# Plaque_Layout.net
KiCad netlist of a schematic drawn in Altium Designer
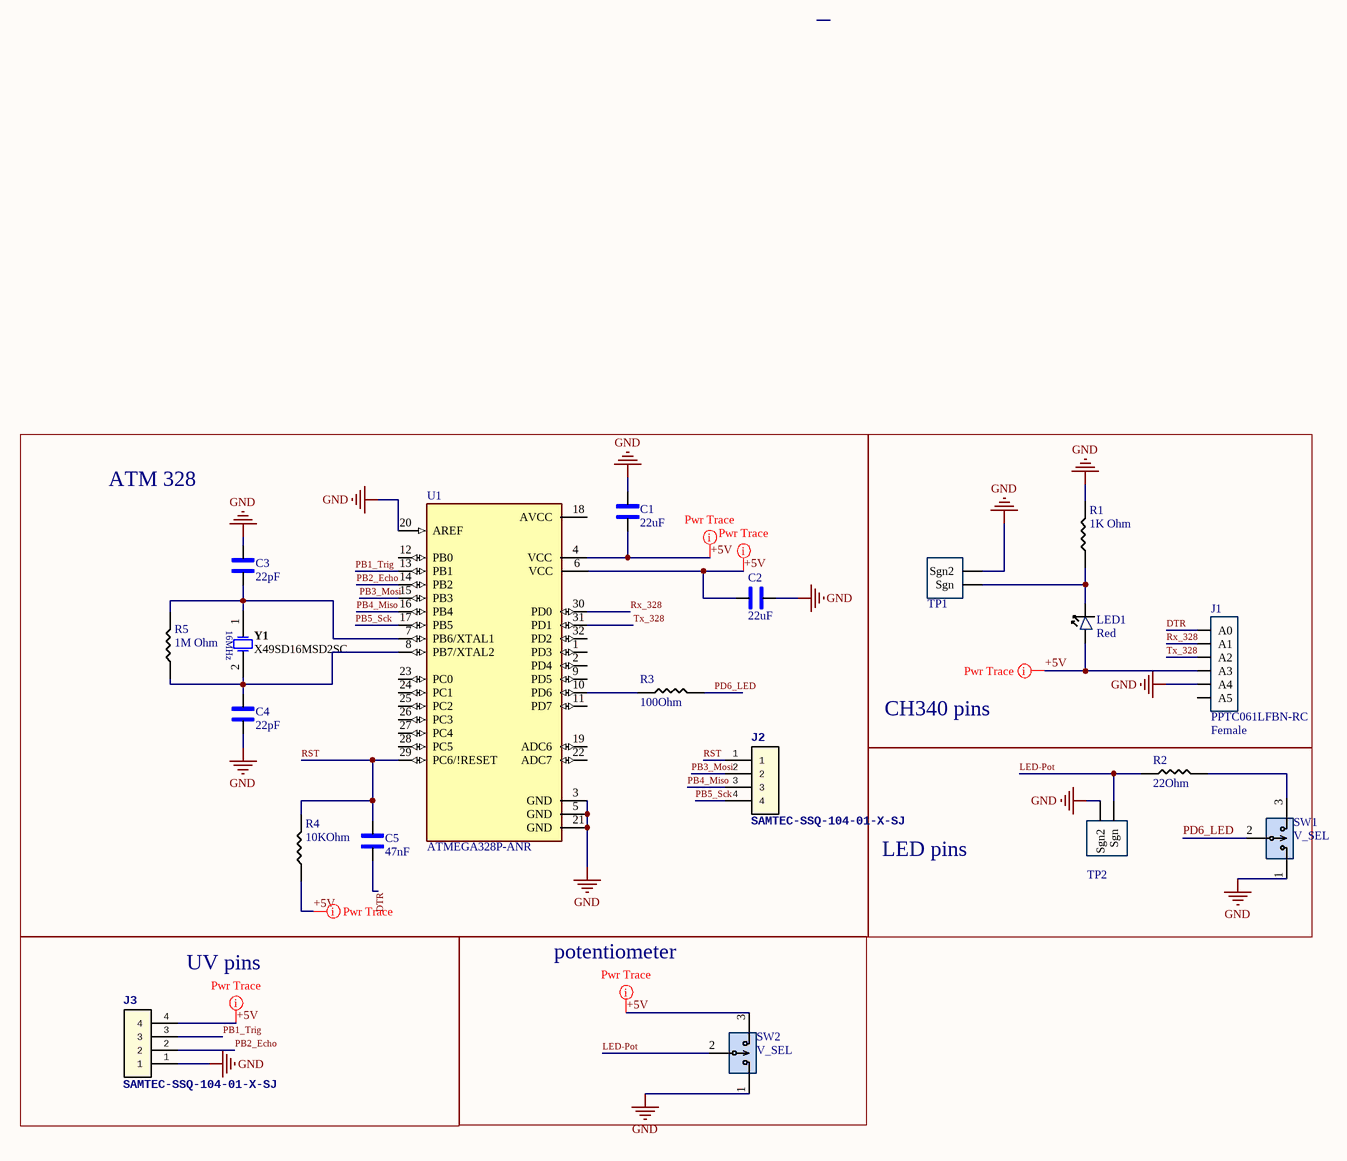
[diagram p0: Plaque_Layout.SchDoc]

(export (version "E")
  (design (tool "Eeschema 10.0.6"))
  (components
    (comp (ref "C1")
      (value "22uF")
      (footprint "1206_Passive_Capacitor")
      (description "22uF ±10% 25V X5R 1206 Multilayer Ceramic Capacitors MLCC - SMD/SMT RoHS")
      (fields (field (name "MFR PART #") "CL31A226KAHNNNE") (field (name "LCSC PART#") "C12891"))
      (libsource (lib "Capstone_Stock_Library") (part "C_22uF_1206"))
    )
    (comp (ref "C2")
      (value "22uF")
      (footprint "1206_Passive_Capacitor")
      (description "22uF ±10% 25V X5R 1206 Multilayer Ceramic Capacitors MLCC - SMD/SMT RoHS")
      (fields (field (name "MFR PART #") "CL31A226KAHNNNE") (field (name "LCSC PART#") "C12891"))
      (libsource (lib "Capstone_Stock_Library") (part "C_22uF_1206"))
    )
    (comp (ref "C3")
      (value "22pF")
      (footprint "1206_Passive_Capacitor")
      (description "50V 22pF C0G ±5% 1206 Multilayer Ceramic Capacitors MLCC - SMD/SMT ROHS")
      (fields (field (name "LCSC PART#") "C107174") (field (name "MFR PART #") "CC1206JKNPOCBN220"))
      (libsource (lib "Capstone_Stock_Library") (part "C_22pF_1206"))
    )
    (comp (ref "C4")
      (value "22pF")
      (footprint "1206_Passive_Capacitor")
      (description "50V 22pF C0G ±5% 1206 Multilayer Ceramic Capacitors MLCC - SMD/SMT ROHS")
      (fields (field (name "LCSC PART#") "C107174") (field (name "MFR PART #") "CC1206JKNPOCBN220"))
      (libsource (lib "Capstone_Stock_Library") (part "C_22pF_1206"))
    )
    (comp (ref "C5")
      (value "47nF")
      (footprint "1206_Passive_Capacitor")
      (description "10nF 50V X7R ±10% 1206 Multilayer Ceramic Capacitors MLCC - SMD/SMT ROHS")
      (fields (field (name "MFR PART #") "CL31B105KBHNNNE") (field (name "LCSC PART#") "C1848"))
      (libsource (lib "Capstone_Stock_Library") (part "C_10nF_1206"))
    )
    (comp (ref "J1")
      (value "PPTC061LFBN-RC")
      (footprint "6_PIN_ARD-Analog_100mil")
      (description "6 Position Header Connector 0.100\" (2.54mm) Through Hole Tin")
      (fields (field (name "LCSC PART#") "C40877") (field (name "ALTIUM_VALUE") "Female"))
      (libsource (lib "Capstone_Stock_Library") (part "JF_6_PIN_FEMA_ARD-Anolog"))
    )
    (comp (ref "J2")
      (value "SAMTEC-SSQ-104-01-X-SJ")
      (footprint "JF-4_SSQ-104-01-X-S")
      (fields (field (name "MFR PART #") "SSQ-104-01-X-SJ") (field (name "LCSC PART#") "C2718488"))
      (libsource (lib "") (part "JF_4_PIN_FEMALE_1"))
    )
    (comp (ref "J3")
      (value "SAMTEC-SSQ-104-01-X-SJ")
      (footprint "JF-4_SSQ-104-01-X-S")
      (fields (field (name "MFR PART #") "SSQ-104-01-X-SJ") (field (name "LCSC PART#") "C2718488"))
      (libsource (lib "Capstone_Stock_Library") (part "JF_4_PIN_FEMALE"))
    )
    (comp (ref "LED1")
      (value "Red")
      (footprint "LED_1206")
      (description "Red 621~631nm 1206 Light Emitting Diodes (LED) RoHS")
      (fields (field (name "MFR PART #") "15-21/R6C-FQ1R1B/2T") (field (name "LCSC PART#") "C93133"))
      (libsource (lib "Capstone_Stock_Library") (part "LED_RED_1206"))
    )
    (comp (ref "R1")
      (value "1K Ohm")
      (footprint "1206_Passive_Resitor")
      (description "CHIP RESISTOR - SURFACE MOUNT 1KOHMS ±1% 1/4W 1206 ROHS")
      (fields (field (name "MFR PART #") "RNCP1206FTD1K00CT") (field (name "LCSC PART#") "C4410"))
      (libsource (lib "Capstone_Stock_Library") (part "R_1K_1206"))
    )
    (comp (ref "R2")
      (value "22Ohm")
      (footprint "1206_Passive_Resitor")
      (description "1Ω ±5% 0.25W ±400ppm/℃ 1206 Chip Resistor - Surface Mount RoHS")
      (fields (field (name "LCSC PART#") "C1409") (field (name "MFR PART #") "1206W4J010JT5E"))
      (libsource (lib "Capstone_Stock_Library") (part "R_1_1206"))
    )
    (comp (ref "R3")
      (value "100Ohm")
      (footprint "1206_Passive_Resitor")
      (description "100Ω ±1% 0.25W ±100ppm/℃ 1206 Chip Resistor - Surface Mount RoHS")
      (fields (field (name "LCSC PART#") "C17901") (field (name "MFR PART #") "1206W4F1000T5E"))
      (libsource (lib "Capstone_Stock_Library") (part "R_100_1206"))
    )
    (comp (ref "R4")
      (value "10KOhm")
      (footprint "1206_Passive_Resitor")
      (description "10 kOhms ±5% 0.25W, 1/4W Chip Resistor 1206 (3216 Metric) Automotive AEC-Q200 Thick Film")
      (fields (field (name "MFR PART #") "RMCF1206FT10K0") (field (name "LCSC PART#") "C17902"))
      (libsource (lib "Capstone_Stock_Library") (part "R_10K_1206"))
    )
    (comp (ref "R5")
      (value "1M Ohm")
      (footprint "1206_Passive_Resitor")
      (description "CHIP RESISTOR - SURFACE MOUNT 1MOHMS ±1% 1/4W 1206 ROHS")
      (fields (field (name "MFR PART #") "RMCF1206JT1M00") (field (name "LCSC PART#") "C17927"))
      (libsource (lib "Capstone_Stock_Library") (part "R_1M_1206"))
    )
    (comp (ref "SW1")
      (value "V_SEL")
      (footprint "3_PIN_100mil")
      (description "Connector Header Through Hole 3 position 0.100\" (2.54mm)")
      (fields (field (name "MFR PART #") "PREC003SAAN-RC") (field (name "LCSC PART#") "C49257"))
      (libsource (lib "328_Arduino_Library") (part "SW_3Pin_100mil_Switch"))
    )
    (comp (ref "SW2")
      (value "V_SEL")
      (footprint "3_PIN_100mil")
      (description "Connector Header Through Hole 3 position 0.100\" (2.54mm)")
      (fields (field (name "MFR PART #") "PREC003SAAN-RC") (field (name "LCSC PART#") "C49257"))
      (libsource (lib "328_Arduino_Library") (part "SW_3Pin_100mil_Switch"))
    )
    (comp (ref "TP1")
      (value "10x Probe TP")
      (footprint "TP_Diff_Probe")
      (description "Test Point 300 mil centers")
      (libsource (lib "") (part "TP_Diff_Probe_1"))
    )
    (comp (ref "TP2")
      (value "10x Probe TP")
      (footprint "TP_Diff_Probe")
      (description "Test Point 300 mil centers")
      (libsource (lib "Capstone_Stock_Library") (part "TP_Diff_Probe"))
    )
    (comp (ref "U1")
      (value "ATMEGA328P-ANR")
      (footprint "ATMega328P")
      (description "AVR AVR® ATmega Microcontroller IC 8-Bit 20MHz 32KB (16K x 16) FLASH 32-TQFP (7x7)")
      (fields (field (name "MFR PART #") "ATMEGA328P-AU") (field (name "LCSC PART#") "C14877"))
      (libsource (lib "Capstone_Stock_Library") (part "U_ATMega328P"))
    )
    (comp (ref "Y1")
      (value "X49SD16MSD2SC")
      (footprint "TH_CRYSTAL")
      (description "16MHz Through Hole Crystal Oscillator (2-pin) 20pF ±20ppm ±30ppm HC-49S Crystals ROHS")
      (fields (field (name "LCSC PART NUMBER") "C16212"))
      (libsource (lib "Capstone_Stock_Library") (part "CRYSTAL_16MHZ_TH_1"))
    )
  )
  (nets
    (net (code "1") (name "/+5V") (class "Default")
      (node (ref "C1") (pin "1") (pinfunction "1_1") (pintype "passive"))
      (node (ref "C2") (pin "1") (pinfunction "1_1") (pintype "passive"))
      (node (ref "J1") (pin "4") (pinfunction "A3_4") (pintype "passive"))
      (node (ref "J3") (pin "4") (pinfunction "4_4") (pintype "passive"))
      (node (ref "LED1") (pin "1") (pinfunction "1_1") (pintype "passive"))
      (node (ref "R4") (pin "1") (pinfunction "1_1") (pintype "passive"))
      (node (ref "SW2") (pin "3") (pinfunction "3_3") (pintype "passive"))
      (node (ref "U1") (pin "4") (pinfunction "VCC_4") (pintype "power_in"))
      (node (ref "U1") (pin "6") (pinfunction "VCC_6") (pintype "power_in"))
    )
    (net (code "2") (name "/DTR") (class "Default")
      (node (ref "C5") (pin "1") (pinfunction "1_1") (pintype "passive"))
      (node (ref "J1") (pin "1") (pinfunction "A0_1") (pintype "passive"))
    )
    (net (code "3") (name "/LED-Pot") (class "Default")
      (node (ref "R2") (pin "1") (pinfunction "1_1") (pintype "passive"))
      (node (ref "SW2") (pin "2") (pinfunction "2_2") (pintype "passive"))
      (node (ref "TP2") (pin "1") (pinfunction "Sgn_1") (pintype "passive"))
    )
    (net (code "4") (name "/PB1_Trig") (class "Default")
      (node (ref "J3") (pin "3") (pinfunction "3_3") (pintype "passive"))
      (node (ref "U1") (pin "13") (pinfunction "PB1_13") (pintype "bidirectional"))
    )
    (net (code "5") (name "/PB2_Echo") (class "Default")
      (node (ref "J3") (pin "2") (pinfunction "2_2") (pintype "passive"))
      (node (ref "U1") (pin "14") (pinfunction "PB2_14") (pintype "bidirectional"))
    )
    (net (code "6") (name "/PB3_Mosi") (class "Default")
      (node (ref "J2") (pin "2") (pinfunction "2_2") (pintype "passive"))
      (node (ref "U1") (pin "15") (pinfunction "PB3_15") (pintype "bidirectional"))
    )
    (net (code "7") (name "/PB4_Miso") (class "Default")
      (node (ref "J2") (pin "3") (pinfunction "3_3") (pintype "passive"))
      (node (ref "U1") (pin "16") (pinfunction "PB4_16") (pintype "bidirectional"))
    )
    (net (code "8") (name "/PB5_Sck") (class "Default")
      (node (ref "J2") (pin "4") (pinfunction "4_4") (pintype "passive"))
      (node (ref "U1") (pin "17") (pinfunction "PB5_17") (pintype "bidirectional"))
    )
    (net (code "9") (name "/PD6_LED") (class "Default")
      (node (ref "R3") (pin "2") (pinfunction "2_2") (pintype "passive"))
      (node (ref "SW1") (pin "2") (pinfunction "2_2") (pintype "passive"))
    )
    (net (code "10") (name "/RST") (class "Default")
      (node (ref "C5") (pin "2") (pinfunction "2_2") (pintype "passive"))
      (node (ref "J2") (pin "1") (pinfunction "1_1") (pintype "passive"))
      (node (ref "R4") (pin "2") (pinfunction "2_2") (pintype "passive"))
      (node (ref "U1") (pin "29") (pinfunction "PC6/!RESET_29") (pintype "bidirectional"))
    )
    (net (code "11") (name "/Rx_328") (class "Default")
      (node (ref "J1") (pin "2") (pinfunction "A1_2") (pintype "passive"))
      (node (ref "U1") (pin "30") (pinfunction "PD0_30") (pintype "bidirectional"))
    )
    (net (code "12") (name "/Tx_328") (class "Default")
      (node (ref "J1") (pin "3") (pinfunction "A2_3") (pintype "passive"))
      (node (ref "U1") (pin "31") (pinfunction "PD1_31") (pintype "bidirectional"))
    )
    (net (code "13") (name "GND") (class "Default")
      (node (ref "C1") (pin "2") (pinfunction "2_2") (pintype "passive"))
      (node (ref "C2") (pin "2") (pinfunction "2_2") (pintype "passive"))
      (node (ref "C3") (pin "2") (pinfunction "2_2") (pintype "passive"))
      (node (ref "C4") (pin "1") (pinfunction "1_1") (pintype "passive"))
      (node (ref "J1") (pin "5") (pinfunction "A4_5") (pintype "passive"))
      (node (ref "J3") (pin "1") (pinfunction "1_1") (pintype "passive"))
      (node (ref "R1") (pin "2") (pinfunction "2_2") (pintype "passive"))
      (node (ref "SW1") (pin "1") (pinfunction "1_1") (pintype "passive"))
      (node (ref "SW2") (pin "1") (pinfunction "1_1") (pintype "passive"))
      (node (ref "TP1") (pin "2") (pinfunction "Sgn2_2") (pintype "passive"))
      (node (ref "TP2") (pin "2") (pinfunction "Sgn2_2") (pintype "passive"))
      (node (ref "U1") (pin "20") (pinfunction "AREF_20") (pintype "input"))
      (node (ref "U1") (pin "21") (pinfunction "GND_21") (pintype "power_in"))
      (node (ref "U1") (pin "3") (pinfunction "GND_3") (pintype "power_in"))
      (node (ref "U1") (pin "5") (pinfunction "GND_5") (pintype "power_in"))
    )
    (net (code "14") (name "Net-(R2-Pad2)") (class "Default")
      (node (ref "R2") (pin "2") (pinfunction "2_2") (pintype "passive"))
      (node (ref "SW1") (pin "3") (pinfunction "3_3") (pintype "passive"))
    )
    (net (code "15") (name "Net-(TP1-Sgn)") (class "Default")
      (node (ref "LED1") (pin "2") (pinfunction "2_2") (pintype "passive"))
      (node (ref "R1") (pin "1") (pinfunction "1_1") (pintype "passive"))
      (node (ref "TP1") (pin "1") (pinfunction "Sgn_1") (pintype "passive"))
    )
    (net (code "16") (name "Net-(U1-PB6{slash}XTAL1)") (class "Default")
      (node (ref "C3") (pin "1") (pinfunction "1_1") (pintype "passive"))
      (node (ref "R5") (pin "2") (pinfunction "2_2") (pintype "passive"))
      (node (ref "U1") (pin "7") (pinfunction "PB6/XTAL1_7") (pintype "bidirectional"))
      (node (ref "Y1") (pin "1") (pinfunction "1_1") (pintype "passive"))
    )
    (net (code "17") (name "Net-(U1-PB7{slash}XTAL2)") (class "Default")
      (node (ref "C4") (pin "2") (pinfunction "2_2") (pintype "passive"))
      (node (ref "R5") (pin "1") (pinfunction "1_1") (pintype "passive"))
      (node (ref "U1") (pin "8") (pinfunction "PB7/XTAL2_8") (pintype "bidirectional"))
      (node (ref "Y1") (pin "2") (pinfunction "2_2") (pintype "passive"))
    )
    (net (code "18") (name "Net-(U1-PD6)") (class "Default")
      (node (ref "R3") (pin "1") (pinfunction "1_1") (pintype "passive"))
      (node (ref "U1") (pin "10") (pinfunction "PD6_10") (pintype "bidirectional"))
    )
    (net (code "19") (name "unconnected-(J1-A5-Pad6)") (class "Default")
      (node (ref "J1") (pin "6") (pinfunction "A5_6") (pintype "passive"))
    )
    (net (code "20") (name "unconnected-(U1-ADC6-Pad19)") (class "Default")
      (node (ref "U1") (pin "19") (pinfunction "ADC6_19") (pintype "bidirectional"))
    )
    (net (code "21") (name "unconnected-(U1-ADC7-Pad22)") (class "Default")
      (node (ref "U1") (pin "22") (pinfunction "ADC7_22") (pintype "bidirectional"))
    )
    (net (code "22") (name "unconnected-(U1-AVCC-Pad18)") (class "Default")
      (node (ref "U1") (pin "18") (pinfunction "AVCC_18") (pintype "power_in"))
    )
    (net (code "23") (name "unconnected-(U1-PB0-Pad12)") (class "Default")
      (node (ref "U1") (pin "12") (pinfunction "PB0_12") (pintype "bidirectional"))
    )
    (net (code "24") (name "unconnected-(U1-PC0-Pad23)") (class "Default")
      (node (ref "U1") (pin "23") (pinfunction "PC0_23") (pintype "bidirectional"))
    )
    (net (code "25") (name "unconnected-(U1-PC1-Pad24)") (class "Default")
      (node (ref "U1") (pin "24") (pinfunction "PC1_24") (pintype "bidirectional"))
    )
    (net (code "26") (name "unconnected-(U1-PC2-Pad25)") (class "Default")
      (node (ref "U1") (pin "25") (pinfunction "PC2_25") (pintype "bidirectional"))
    )
    (net (code "27") (name "unconnected-(U1-PC3-Pad26)") (class "Default")
      (node (ref "U1") (pin "26") (pinfunction "PC3_26") (pintype "bidirectional"))
    )
    (net (code "28") (name "unconnected-(U1-PC4-Pad27)") (class "Default")
      (node (ref "U1") (pin "27") (pinfunction "PC4_27") (pintype "bidirectional"))
    )
    (net (code "29") (name "unconnected-(U1-PC5-Pad28)") (class "Default")
      (node (ref "U1") (pin "28") (pinfunction "PC5_28") (pintype "bidirectional"))
    )
    (net (code "30") (name "unconnected-(U1-PD2-Pad32)") (class "Default")
      (node (ref "U1") (pin "32") (pinfunction "PD2_32") (pintype "bidirectional"))
    )
    (net (code "31") (name "unconnected-(U1-PD3-Pad1)") (class "Default")
      (node (ref "U1") (pin "1") (pinfunction "PD3_1") (pintype "bidirectional"))
    )
    (net (code "32") (name "unconnected-(U1-PD4-Pad2)") (class "Default")
      (node (ref "U1") (pin "2") (pinfunction "PD4_2") (pintype "bidirectional"))
    )
    (net (code "33") (name "unconnected-(U1-PD5-Pad9)") (class "Default")
      (node (ref "U1") (pin "9") (pinfunction "PD5_9") (pintype "bidirectional"))
    )
    (net (code "34") (name "unconnected-(U1-PD7-Pad11)") (class "Default")
      (node (ref "U1") (pin "11") (pinfunction "PD7_11") (pintype "bidirectional"))
    )
  )
)
